# BMS.net
KiCad netlist of a schematic drawn in EAGLE
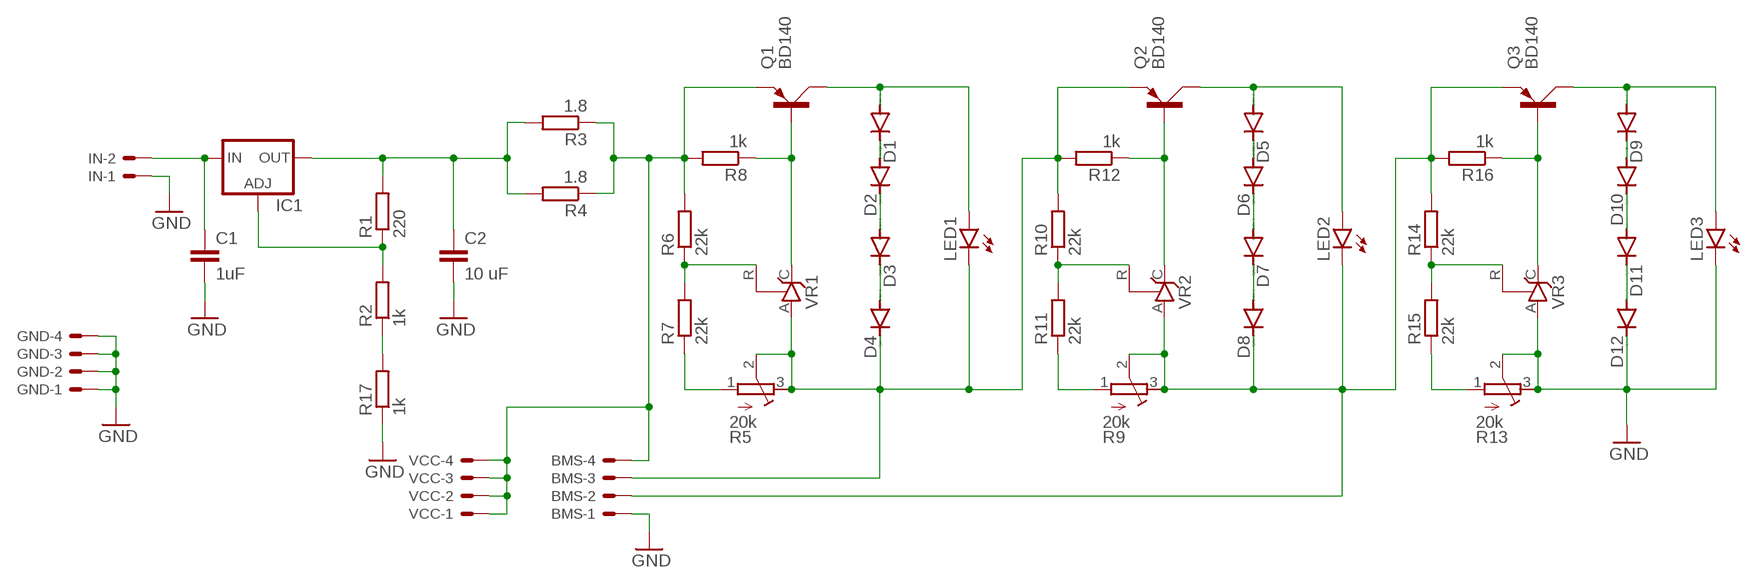
[diagram p0: schematic, sheet 1]

(export (version "E")
  (design (tool "Eeschema 10.0.6"))
  (components
    (comp (ref "BMS")
      (value "22-23-2041")
      (footprint "eagle-import:22-23-2041")
      (fields (field (name "MF") "MOLEX"))
      (libsource (lib "eagle-import") (part "22-23-2041"))
    )
    (comp (ref "C1")
      (value "1uF")
      (footprint "eagle-import:C025-025X050")
      (libsource (lib "eagle-import") (part "C-EU025-025X050"))
    )
    (comp (ref "C2")
      (value "10 uF")
      (footprint "eagle-import:C025-025X050")
      (libsource (lib "eagle-import") (part "C-EU025-025X050"))
    )
    (comp (ref "D1")
      (value "1N4004")
      (footprint "eagle-import:DO41-10")
      (libsource (lib "eagle-import") (part "1N4004"))
    )
    (comp (ref "D2")
      (value "1N4004")
      (footprint "eagle-import:DO41-10")
      (libsource (lib "eagle-import") (part "1N4004"))
    )
    (comp (ref "D3")
      (value "1N4004")
      (footprint "eagle-import:DO41-10")
      (libsource (lib "eagle-import") (part "1N4004"))
    )
    (comp (ref "D4")
      (value "1N4004")
      (footprint "eagle-import:DO41-10")
      (libsource (lib "eagle-import") (part "1N4004"))
    )
    (comp (ref "D5")
      (value "1N4004")
      (footprint "eagle-import:DO41-10")
      (libsource (lib "eagle-import") (part "1N4004"))
    )
    (comp (ref "D6")
      (value "1N4004")
      (footprint "eagle-import:DO41-10")
      (libsource (lib "eagle-import") (part "1N4004"))
    )
    (comp (ref "D7")
      (value "1N4004")
      (footprint "eagle-import:DO41-10")
      (libsource (lib "eagle-import") (part "1N4004"))
    )
    (comp (ref "D8")
      (value "1N4004")
      (footprint "eagle-import:DO41-10")
      (libsource (lib "eagle-import") (part "1N4004"))
    )
    (comp (ref "D9")
      (value "1N4004")
      (footprint "eagle-import:DO41-10")
      (libsource (lib "eagle-import") (part "1N4004"))
    )
    (comp (ref "D10")
      (value "1N4004")
      (footprint "eagle-import:DO41-10")
      (libsource (lib "eagle-import") (part "1N4004"))
    )
    (comp (ref "D11")
      (value "1N4004")
      (footprint "eagle-import:DO41-10")
      (libsource (lib "eagle-import") (part "1N4004"))
    )
    (comp (ref "D12")
      (value "1N4004")
      (footprint "eagle-import:DO41-10")
      (libsource (lib "eagle-import") (part "1N4004"))
    )
    (comp (ref "GND")
      (value "22-23-2041")
      (footprint "eagle-import:22-23-2041")
      (fields (field (name "MF") "MOLEX"))
      (libsource (lib "eagle-import") (part "22-23-2041"))
    )
    (comp (ref "IC1")
      (value "LM317TS")
      (footprint "eagle-import:317TS")
      (libsource (lib "eagle-import") (part "LM317TS"))
    )
    (comp (ref "IN")
      (value "22-23-2021")
      (footprint "eagle-import:22-23-2021")
      (fields (field (name "MF") "MOLEX"))
      (libsource (lib "eagle-import") (part "22-23-2021"))
    )
    (comp (ref "LED1")
      (value "LED5MM")
      (footprint "eagle-import:LED5MM")
      (libsource (lib "eagle-import") (part "LED5MM"))
    )
    (comp (ref "LED2")
      (value "LED5MM")
      (footprint "eagle-import:LED5MM")
      (libsource (lib "eagle-import") (part "LED5MM"))
    )
    (comp (ref "LED3")
      (value "LED5MM")
      (footprint "eagle-import:LED5MM")
      (libsource (lib "eagle-import") (part "LED5MM"))
    )
    (comp (ref "Q1")
      (value "BD140")
      (footprint "eagle-import:TO126AV")
      (libsource (lib "eagle-import") (part "BD140"))
    )
    (comp (ref "Q2")
      (value "BD140")
      (footprint "eagle-import:TO126AV")
      (libsource (lib "eagle-import") (part "BD140"))
    )
    (comp (ref "Q3")
      (value "BD140")
      (footprint "eagle-import:TO126AV")
      (libsource (lib "eagle-import") (part "BD140"))
    )
    (comp (ref "R1")
      (value "220")
      (footprint "eagle-import:0207_10")
      (libsource (lib "eagle-import") (part "R-EU_0207/10"))
    )
    (comp (ref "R2")
      (value "1k")
      (footprint "eagle-import:0207_10")
      (libsource (lib "eagle-import") (part "R-EU_0207/10"))
    )
    (comp (ref "R3")
      (value "1.8")
      (footprint "eagle-import:0617_22")
      (libsource (lib "eagle-import") (part "R-EU_0617/22"))
    )
    (comp (ref "R4")
      (value "1.8")
      (footprint "eagle-import:0617_22")
      (libsource (lib "eagle-import") (part "R-EU_0617/22"))
    )
    (comp (ref "R5")
      (value "20k")
      (footprint "eagle-import:RTRIM3296W")
      (libsource (lib "eagle-import") (part "R-TRIMM3296W"))
    )
    (comp (ref "R6")
      (value "22k")
      (footprint "eagle-import:0207_10")
      (libsource (lib "eagle-import") (part "R-EU_0207/10"))
    )
    (comp (ref "R7")
      (value "22k")
      (footprint "eagle-import:0207_10")
      (libsource (lib "eagle-import") (part "R-EU_0207/10"))
    )
    (comp (ref "R8")
      (value "1k")
      (footprint "eagle-import:0207_10")
      (libsource (lib "eagle-import") (part "R-EU_0207/10"))
    )
    (comp (ref "R9")
      (value "20k")
      (footprint "eagle-import:RTRIM3296W")
      (libsource (lib "eagle-import") (part "R-TRIMM3296W"))
    )
    (comp (ref "R10")
      (value "22k")
      (footprint "eagle-import:0207_10")
      (libsource (lib "eagle-import") (part "R-EU_0207/10"))
    )
    (comp (ref "R11")
      (value "22k")
      (footprint "eagle-import:0207_10")
      (libsource (lib "eagle-import") (part "R-EU_0207/10"))
    )
    (comp (ref "R12")
      (value "1k")
      (footprint "eagle-import:0207_10")
      (libsource (lib "eagle-import") (part "R-EU_0207/10"))
    )
    (comp (ref "R13")
      (value "20k")
      (footprint "eagle-import:RTRIM3296W")
      (libsource (lib "eagle-import") (part "R-TRIMM3296W"))
    )
    (comp (ref "R14")
      (value "22k")
      (footprint "eagle-import:0207_10")
      (libsource (lib "eagle-import") (part "R-EU_0207/10"))
    )
    (comp (ref "R15")
      (value "22k")
      (footprint "eagle-import:0207_10")
      (libsource (lib "eagle-import") (part "R-EU_0207/10"))
    )
    (comp (ref "R16")
      (value "1k")
      (footprint "eagle-import:0207_10")
      (libsource (lib "eagle-import") (part "R-EU_0207/10"))
    )
    (comp (ref "R17")
      (value "1k")
      (footprint "eagle-import:0207_10")
      (libsource (lib "eagle-import") (part "R-EU_0207/10"))
    )
    (comp (ref "VCC")
      (value "22-23-2041")
      (footprint "eagle-import:22-23-2041")
      (fields (field (name "MF") "MOLEX"))
      (libsource (lib "eagle-import") (part "22-23-2041"))
    )
    (comp (ref "VR1")
      (value "TL431CLP")
      (footprint "eagle-import:TO92-CLP")
      (libsource (lib "eagle-import") (part "TL431CLP"))
    )
    (comp (ref "VR2")
      (value "TL431CLP")
      (footprint "eagle-import:TO92-CLP")
      (libsource (lib "eagle-import") (part "TL431CLP"))
    )
    (comp (ref "VR3")
      (value "TL431CLP")
      (footprint "eagle-import:TO92-CLP")
      (libsource (lib "eagle-import") (part "TL431CLP"))
    )
  )
  (nets
    (net (code "1") (name "GND") (class "Default")
      (node (ref "BMS") (pin "1") (pinfunction "S_1") (pintype "passive"))
      (node (ref "C1") (pin "2") (pinfunction "2_2") (pintype "passive"))
      (node (ref "C2") (pin "2") (pinfunction "2_2") (pintype "passive"))
      (node (ref "D12") (pin "C") (pinfunction "C_C") (pintype "passive"))
      (node (ref "GND") (pin "1") (pinfunction "S_1") (pintype "passive"))
      (node (ref "GND") (pin "2") (pinfunction "S_2") (pintype "passive"))
      (node (ref "GND") (pin "3") (pinfunction "S_3") (pintype "passive"))
      (node (ref "GND") (pin "4") (pinfunction "S_4") (pintype "passive"))
      (node (ref "IN") (pin "1") (pinfunction "S_1") (pintype "passive"))
      (node (ref "LED3") (pin "K") (pinfunction "C_K") (pintype "passive"))
      (node (ref "R13") (pin "2") (pinfunction "S_2") (pintype "passive"))
      (node (ref "R13") (pin "3") (pinfunction "E_3") (pintype "passive"))
      (node (ref "R17") (pin "1") (pinfunction "1_1") (pintype "passive"))
      (node (ref "VR3") (pin "A") (pinfunction "A_A") (pintype "passive"))
    )
    (net (code "2") (name "Net-(BMSB-S)") (class "Default")
      (node (ref "BMS") (pin "2") (pinfunction "S_2") (pintype "passive"))
      (node (ref "D8") (pin "C") (pinfunction "C_C") (pintype "passive"))
      (node (ref "LED2") (pin "K") (pinfunction "C_K") (pintype "passive"))
      (node (ref "Q3") (pin "E") (pinfunction "E_E") (pintype "passive"))
      (node (ref "R14") (pin "2") (pinfunction "2_2") (pintype "passive"))
      (node (ref "R16") (pin "2") (pinfunction "2_2") (pintype "passive"))
      (node (ref "R9") (pin "2") (pinfunction "S_2") (pintype "passive"))
      (node (ref "R9") (pin "3") (pinfunction "E_3") (pintype "passive"))
      (node (ref "VR2") (pin "A") (pinfunction "A_A") (pintype "passive"))
    )
    (net (code "3") (name "Net-(BMSC-S)") (class "Default")
      (node (ref "BMS") (pin "3") (pinfunction "S_3") (pintype "passive"))
      (node (ref "D4") (pin "C") (pinfunction "C_C") (pintype "passive"))
      (node (ref "LED1") (pin "K") (pinfunction "C_K") (pintype "passive"))
      (node (ref "Q2") (pin "E") (pinfunction "E_E") (pintype "passive"))
      (node (ref "R10") (pin "2") (pinfunction "2_2") (pintype "passive"))
      (node (ref "R12") (pin "2") (pinfunction "2_2") (pintype "passive"))
      (node (ref "R5") (pin "2") (pinfunction "S_2") (pintype "passive"))
      (node (ref "R5") (pin "3") (pinfunction "E_3") (pintype "passive"))
      (node (ref "VR1") (pin "A") (pinfunction "A_A") (pintype "passive"))
    )
    (net (code "4") (name "Net-(BMSD-S)") (class "Default")
      (node (ref "BMS") (pin "4") (pinfunction "S_4") (pintype "passive"))
      (node (ref "Q1") (pin "E") (pinfunction "E_E") (pintype "passive"))
      (node (ref "R3") (pin "1") (pinfunction "1_1") (pintype "passive"))
      (node (ref "R4") (pin "1") (pinfunction "1_1") (pintype "passive"))
      (node (ref "R6") (pin "2") (pinfunction "2_2") (pintype "passive"))
      (node (ref "R8") (pin "2") (pinfunction "2_2") (pintype "passive"))
      (node (ref "VCC") (pin "1") (pinfunction "S_1") (pintype "passive"))
      (node (ref "VCC") (pin "2") (pinfunction "S_2") (pintype "passive"))
      (node (ref "VCC") (pin "3") (pinfunction "S_3") (pintype "passive"))
      (node (ref "VCC") (pin "4") (pinfunction "S_4") (pintype "passive"))
    )
    (net (code "5") (name "Net-(D1-PadA)") (class "Default")
      (node (ref "D1") (pin "A") (pinfunction "A_A") (pintype "passive"))
      (node (ref "LED1") (pin "A") (pinfunction "A_A") (pintype "passive"))
      (node (ref "Q1") (pin "C") (pinfunction "C_C") (pintype "passive"))
    )
    (net (code "6") (name "Net-(D1-PadC)") (class "Default")
      (node (ref "D1") (pin "C") (pinfunction "C_C") (pintype "passive"))
      (node (ref "D2") (pin "A") (pinfunction "A_A") (pintype "passive"))
    )
    (net (code "7") (name "Net-(D2-PadC)") (class "Default")
      (node (ref "D2") (pin "C") (pinfunction "C_C") (pintype "passive"))
      (node (ref "D3") (pin "A") (pinfunction "A_A") (pintype "passive"))
    )
    (net (code "8") (name "Net-(D3-PadC)") (class "Default")
      (node (ref "D3") (pin "C") (pinfunction "C_C") (pintype "passive"))
      (node (ref "D4") (pin "A") (pinfunction "A_A") (pintype "passive"))
    )
    (net (code "9") (name "Net-(D5-PadA)") (class "Default")
      (node (ref "D5") (pin "A") (pinfunction "A_A") (pintype "passive"))
      (node (ref "LED2") (pin "A") (pinfunction "A_A") (pintype "passive"))
      (node (ref "Q2") (pin "C") (pinfunction "C_C") (pintype "passive"))
    )
    (net (code "10") (name "Net-(D5-PadC)") (class "Default")
      (node (ref "D5") (pin "C") (pinfunction "C_C") (pintype "passive"))
      (node (ref "D6") (pin "A") (pinfunction "A_A") (pintype "passive"))
    )
    (net (code "11") (name "Net-(D6-PadC)") (class "Default")
      (node (ref "D6") (pin "C") (pinfunction "C_C") (pintype "passive"))
      (node (ref "D7") (pin "A") (pinfunction "A_A") (pintype "passive"))
    )
    (net (code "12") (name "Net-(D7-PadC)") (class "Default")
      (node (ref "D7") (pin "C") (pinfunction "C_C") (pintype "passive"))
      (node (ref "D8") (pin "A") (pinfunction "A_A") (pintype "passive"))
    )
    (net (code "13") (name "Net-(D9-PadA)") (class "Default")
      (node (ref "D9") (pin "A") (pinfunction "A_A") (pintype "passive"))
      (node (ref "LED3") (pin "A") (pinfunction "A_A") (pintype "passive"))
      (node (ref "Q3") (pin "C") (pinfunction "C_C") (pintype "passive"))
    )
    (net (code "14") (name "Net-(D10-PadA)") (class "Default")
      (node (ref "D10") (pin "A") (pinfunction "A_A") (pintype "passive"))
      (node (ref "D9") (pin "C") (pinfunction "C_C") (pintype "passive"))
    )
    (net (code "15") (name "Net-(D10-PadC)") (class "Default")
      (node (ref "D10") (pin "C") (pinfunction "C_C") (pintype "passive"))
      (node (ref "D11") (pin "A") (pinfunction "A_A") (pintype "passive"))
    )
    (net (code "16") (name "Net-(D11-PadC)") (class "Default")
      (node (ref "D11") (pin "C") (pinfunction "C_C") (pintype "passive"))
      (node (ref "D12") (pin "A") (pinfunction "A_A") (pintype "passive"))
    )
    (net (code "17") (name "Net-(IC1-ADJ)") (class "Default")
      (node (ref "IC1") (pin "1") (pinfunction "ADJ_1") (pintype "input"))
      (node (ref "R1") (pin "1") (pinfunction "1_1") (pintype "passive"))
      (node (ref "R2") (pin "2") (pinfunction "2_2") (pintype "passive"))
    )
    (net (code "18") (name "Net-(IC1-IN)") (class "Default")
      (node (ref "C1") (pin "1") (pinfunction "1_1") (pintype "passive"))
      (node (ref "IC1") (pin "3") (pinfunction "IN_3") (pintype "input"))
      (node (ref "IN") (pin "2") (pinfunction "S_2") (pintype "passive"))
    )
    (net (code "19") (name "Net-(IC1-OUT)") (class "Default")
      (node (ref "C2") (pin "1") (pinfunction "1_1") (pintype "passive"))
      (node (ref "IC1") (pin "2") (pinfunction "OUT_2") (pintype "passive"))
      (node (ref "R1") (pin "2") (pinfunction "2_2") (pintype "passive"))
      (node (ref "R3") (pin "2") (pinfunction "2_2") (pintype "passive"))
      (node (ref "R4") (pin "2") (pinfunction "2_2") (pintype "passive"))
    )
    (net (code "20") (name "Net-(Q1-PadB)") (class "Default")
      (node (ref "Q1") (pin "B") (pinfunction "B_B") (pintype "passive"))
      (node (ref "R8") (pin "1") (pinfunction "1_1") (pintype "passive"))
      (node (ref "VR1") (pin "C") (pinfunction "C_C") (pintype "passive"))
    )
    (net (code "21") (name "Net-(Q2-PadB)") (class "Default")
      (node (ref "Q2") (pin "B") (pinfunction "B_B") (pintype "passive"))
      (node (ref "R12") (pin "1") (pinfunction "1_1") (pintype "passive"))
      (node (ref "VR2") (pin "C") (pinfunction "C_C") (pintype "passive"))
    )
    (net (code "22") (name "Net-(Q3-PadB)") (class "Default")
      (node (ref "Q3") (pin "B") (pinfunction "B_B") (pintype "passive"))
      (node (ref "R16") (pin "1") (pinfunction "1_1") (pintype "passive"))
      (node (ref "VR3") (pin "C") (pinfunction "C_C") (pintype "passive"))
    )
    (net (code "23") (name "Net-(R5-A)") (class "Default")
      (node (ref "R5") (pin "1") (pinfunction "A_1") (pintype "passive"))
      (node (ref "R7") (pin "1") (pinfunction "1_1") (pintype "passive"))
    )
    (net (code "24") (name "Net-(R6-Pad1)") (class "Default")
      (node (ref "R6") (pin "1") (pinfunction "1_1") (pintype "passive"))
      (node (ref "R7") (pin "2") (pinfunction "2_2") (pintype "passive"))
      (node (ref "VR1") (pin "R") (pinfunction "R_R") (pintype "passive"))
    )
    (net (code "25") (name "Net-(R9-A)") (class "Default")
      (node (ref "R11") (pin "1") (pinfunction "1_1") (pintype "passive"))
      (node (ref "R9") (pin "1") (pinfunction "A_1") (pintype "passive"))
    )
    (net (code "26") (name "Net-(R10-Pad1)") (class "Default")
      (node (ref "R10") (pin "1") (pinfunction "1_1") (pintype "passive"))
      (node (ref "R11") (pin "2") (pinfunction "2_2") (pintype "passive"))
      (node (ref "VR2") (pin "R") (pinfunction "R_R") (pintype "passive"))
    )
    (net (code "27") (name "Net-(R13-A)") (class "Default")
      (node (ref "R13") (pin "1") (pinfunction "A_1") (pintype "passive"))
      (node (ref "R15") (pin "1") (pinfunction "1_1") (pintype "passive"))
    )
    (net (code "28") (name "Net-(R14-Pad1)") (class "Default")
      (node (ref "R14") (pin "1") (pinfunction "1_1") (pintype "passive"))
      (node (ref "R15") (pin "2") (pinfunction "2_2") (pintype "passive"))
      (node (ref "VR3") (pin "R") (pinfunction "R_R") (pintype "passive"))
    )
    (net (code "29") (name "Net-(R17-Pad2)") (class "Default")
      (node (ref "R17") (pin "2") (pinfunction "2_2") (pintype "passive"))
      (node (ref "R2") (pin "1") (pinfunction "1_1") (pintype "passive"))
    )
  )
)
